# phrike.net
KiCad netlist of a schematic drawn in EAGLE
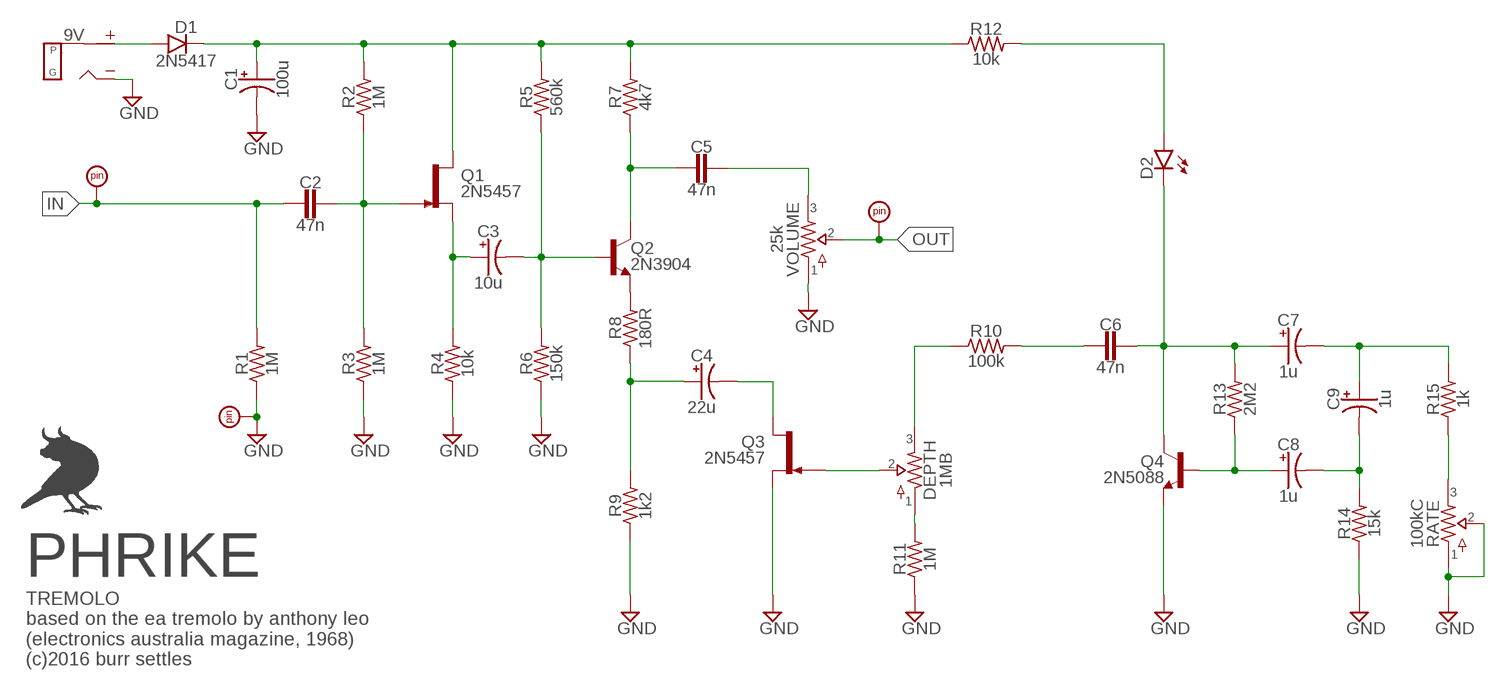
[diagram p0: schematic, sheet 1]

(export (version "E")
  (design (tool "Eeschema 10.0.6"))
  (components
    (comp (ref "9V")
      (value "DC_MONO")
      (footprint "eagle-import:DC")
      (libsource (lib "eagle-import") (part "DC_MONO"))
    )
    (comp (ref "C1")
      (value "100u")
      (footprint "eagle-import:063_025")
      (libsource (lib "eagle-import") (part "0631"))
    )
    (comp (ref "C2")
      (value "47n")
      (footprint "eagle-import:050X030_025_2")
      (libsource (lib "eagle-import") (part "CER/FILM2"))
    )
    (comp (ref "C3")
      (value "10u")
      (footprint "eagle-import:050_020_1")
      (libsource (lib "eagle-import") (part "0501"))
    )
    (comp (ref "C4")
      (value "22u")
      (footprint "eagle-import:050_020_1")
      (libsource (lib "eagle-import") (part "0501"))
    )
    (comp (ref "C5")
      (value "47n")
      (footprint "eagle-import:050X030_025_2")
      (libsource (lib "eagle-import") (part "CER/FILM2"))
    )
    (comp (ref "C6")
      (value "47n")
      (footprint "eagle-import:050X030_025_2")
      (libsource (lib "eagle-import") (part "CER/FILM2"))
    )
    (comp (ref "C7")
      (value "1u")
      (footprint "eagle-import:050_020_1")
      (libsource (lib "eagle-import") (part "0501"))
    )
    (comp (ref "C8")
      (value "1u")
      (footprint "eagle-import:050_020_1")
      (libsource (lib "eagle-import") (part "0501"))
    )
    (comp (ref "C9")
      (value "1u")
      (footprint "eagle-import:050_020_1")
      (libsource (lib "eagle-import") (part "0501"))
    )
    (comp (ref "D1")
      (value "2N5417")
      (footprint "eagle-import:DO41-3")
      (libsource (lib "eagle-import") (part "DO41.3"))
    )
    (comp (ref "D2")
      (value "LEDA")
      (footprint "eagle-import:3MM_A")
      (libsource (lib "eagle-import") (part "LEDA"))
    )
    (comp (ref "DEPTH")
      (value "1MB")
      (footprint "eagle-import:2262_TRIM")
      (libsource (lib "eagle-import") (part "POTSTRIM"))
    )
    (comp (ref "GND")
      (value "PADRND")
      (footprint "eagle-import:ROUND")
      (libsource (lib "eagle-import") (part "PADRND"))
    )
    (comp (ref "IN")
      (value "PADSQR")
      (footprint "eagle-import:SQUARE")
      (libsource (lib "eagle-import") (part "PADSQR"))
    )
    (comp (ref "OUT")
      (value "PADSQR")
      (footprint "eagle-import:SQUARE")
      (libsource (lib "eagle-import") (part "PADSQR"))
    )
    (comp (ref "Q1")
      (value "2N5457")
      (footprint "eagle-import:TO92-")
      (libsource (lib "eagle-import") (part "2N5457"))
    )
    (comp (ref "Q2")
      (value "2N3904")
      (footprint "eagle-import:TO92-L2")
      (libsource (lib "eagle-import") (part "2N3904L2"))
    )
    (comp (ref "Q3")
      (value "2N5457")
      (footprint "eagle-import:TO92-")
      (libsource (lib "eagle-import") (part "2N5457"))
    )
    (comp (ref "Q4")
      (value "2N5088")
      (footprint "eagle-import:TO92-")
      (libsource (lib "eagle-import") (part "2N5088"))
    )
    (comp (ref "R1")
      (value "1M")
      (footprint "eagle-import:R0207_3")
      (libsource (lib "eagle-import") (part "R_.3B"))
    )
    (comp (ref "R2")
      (value "1M")
      (footprint "eagle-import:R0207_3")
      (libsource (lib "eagle-import") (part "R_.3B"))
    )
    (comp (ref "R3")
      (value "1M")
      (footprint "eagle-import:R0207_3")
      (libsource (lib "eagle-import") (part "R_.3B"))
    )
    (comp (ref "R4")
      (value "10k")
      (footprint "eagle-import:R0207_3")
      (libsource (lib "eagle-import") (part "R_.3B"))
    )
    (comp (ref "R5")
      (value "560k")
      (footprint "eagle-import:R0207_3")
      (libsource (lib "eagle-import") (part "R_.3B"))
    )
    (comp (ref "R6")
      (value "150k")
      (footprint "eagle-import:R0207_3")
      (libsource (lib "eagle-import") (part "R_.3B"))
    )
    (comp (ref "R7")
      (value "4k7")
      (footprint "eagle-import:R0207_3")
      (libsource (lib "eagle-import") (part "R_.3B"))
    )
    (comp (ref "R8")
      (value "180R")
      (footprint "eagle-import:R0207_3")
      (libsource (lib "eagle-import") (part "R_.3B"))
    )
    (comp (ref "R9")
      (value "1k2")
      (footprint "eagle-import:R0207_3")
      (libsource (lib "eagle-import") (part "R_.3B"))
    )
    (comp (ref "R10")
      (value "100k")
      (footprint "eagle-import:R0207_3")
      (libsource (lib "eagle-import") (part "R_.3B"))
    )
    (comp (ref "R11")
      (value "1M")
      (footprint "eagle-import:R0207_3")
      (libsource (lib "eagle-import") (part "R_.3B"))
    )
    (comp (ref "R12")
      (value "10k")
      (footprint "eagle-import:R0207_3")
      (libsource (lib "eagle-import") (part "R_.3B"))
    )
    (comp (ref "R13")
      (value "2M2")
      (footprint "eagle-import:R0207_3")
      (libsource (lib "eagle-import") (part "R_.3B"))
    )
    (comp (ref "R14")
      (value "15k")
      (footprint "eagle-import:R0207_3")
      (libsource (lib "eagle-import") (part "R_.3B"))
    )
    (comp (ref "R15")
      (value "1k")
      (footprint "eagle-import:R0207_3")
      (libsource (lib "eagle-import") (part "R_.3B"))
    )
    (comp (ref "RATE")
      (value "100kC")
      (footprint "eagle-import:PADS_SMALL")
      (libsource (lib "eagle-import") (part "POTSSMALL_PADS"))
    )
    (comp (ref "VOLUME")
      (value "25k")
      (footprint "eagle-import:2262_TRIM")
      (libsource (lib "eagle-import") (part "POTSTRIM"))
    )
  )
  (nets
    (net (code "1") (name "GND") (class "Default")
      (node (ref "9V") (pin "S") (pinfunction "SLEEVE_S") (pintype "passive"))
      (node (ref "C1") (pin "-") (pinfunction "-_-") (pintype "passive"))
      (node (ref "GND") (pin "1") (pinfunction "P$1_1") (pintype "bidirectional"))
      (node (ref "Q3") (pin "2") (pinfunction "S_2") (pintype "passive"))
      (node (ref "Q4") (pin "3") (pinfunction "E_3") (pintype "passive"))
      (node (ref "R1") (pin "1") (pinfunction "1_1") (pintype "passive"))
      (node (ref "R11") (pin "1") (pinfunction "1_1") (pintype "passive"))
      (node (ref "R14") (pin "1") (pinfunction "1_1") (pintype "passive"))
      (node (ref "R3") (pin "1") (pinfunction "1_1") (pintype "passive"))
      (node (ref "R4") (pin "1") (pinfunction "1_1") (pintype "passive"))
      (node (ref "R6") (pin "1") (pinfunction "1_1") (pintype "passive"))
      (node (ref "R9") (pin "1") (pinfunction "1_1") (pintype "passive"))
      (node (ref "RATE") (pin "1") (pinfunction "1_1") (pintype "passive"))
      (node (ref "RATE") (pin "2") (pinfunction "2_2") (pintype "passive"))
      (node (ref "VOLUME") (pin "1") (pinfunction "1_1") (pintype "passive"))
    )
    (net (code "2") (name "IN") (class "Default")
      (node (ref "C2") (pin "2") (pinfunction "2_2") (pintype "passive"))
      (node (ref "IN") (pin "1") (pinfunction "P$1_1") (pintype "bidirectional"))
      (node (ref "R1") (pin "2") (pinfunction "2_2") (pintype "passive"))
    )
    (net (code "3") (name "Net-(9V-TIP)") (class "Default")
      (node (ref "9V") (pin "T") (pinfunction "TIP_T") (pintype "passive"))
      (node (ref "D1") (pin "A") (pinfunction "A_A") (pintype "passive"))
    )
    (net (code "4") (name "Net-(C4-Pad+)") (class "Default")
      (node (ref "C4") (pin "+") (pinfunction "+_+") (pintype "passive"))
      (node (ref "R8") (pin "1") (pinfunction "1_1") (pintype "passive"))
      (node (ref "R9") (pin "2") (pinfunction "2_2") (pintype "passive"))
    )
    (net (code "5") (name "Net-(C5-Pad1)") (class "Default")
      (node (ref "C5") (pin "1") (pinfunction "1_1") (pintype "passive"))
      (node (ref "VOLUME") (pin "3") (pinfunction "3_3") (pintype "passive"))
    )
    (net (code "6") (name "Net-(C6-Pad2)") (class "Default")
      (node (ref "C6") (pin "2") (pinfunction "2_2") (pintype "passive"))
      (node (ref "R10") (pin "2") (pinfunction "2_2") (pintype "passive"))
    )
    (net (code "7") (name "Net-(C7-Pad-)") (class "Default")
      (node (ref "C7") (pin "-") (pinfunction "-_-") (pintype "passive"))
      (node (ref "C9") (pin "+") (pinfunction "+_+") (pintype "passive"))
      (node (ref "R15") (pin "2") (pinfunction "2_2") (pintype "passive"))
    )
    (net (code "8") (name "Net-(C8-Pad-)") (class "Default")
      (node (ref "C8") (pin "-") (pinfunction "-_-") (pintype "passive"))
      (node (ref "C9") (pin "-") (pinfunction "-_-") (pintype "passive"))
      (node (ref "R14") (pin "2") (pinfunction "2_2") (pintype "passive"))
    )
    (net (code "9") (name "Net-(D2-C)") (class "Default")
      (node (ref "C6") (pin "1") (pinfunction "1_1") (pintype "passive"))
      (node (ref "C7") (pin "+") (pinfunction "+_+") (pintype "passive"))
      (node (ref "D2") (pin "K") (pinfunction "C_K") (pintype "passive"))
      (node (ref "Q4") (pin "1") (pinfunction "C_1") (pintype "passive"))
      (node (ref "R13") (pin "2") (pinfunction "2_2") (pintype "passive"))
    )
    (net (code "10") (name "Net-(D2-PadA)") (class "Default")
      (node (ref "D2") (pin "A") (pinfunction "A_A") (pintype "passive"))
      (node (ref "R12") (pin "2") (pinfunction "2_2") (pintype "passive"))
    )
    (net (code "11") (name "Net-(DEPTH-Pad1)") (class "Default")
      (node (ref "DEPTH") (pin "1") (pinfunction "1_1") (pintype "passive"))
      (node (ref "R11") (pin "2") (pinfunction "2_2") (pintype "passive"))
    )
    (net (code "12") (name "Net-(DEPTH-Pad3)") (class "Default")
      (node (ref "DEPTH") (pin "3") (pinfunction "3_3") (pintype "passive"))
      (node (ref "R10") (pin "1") (pinfunction "1_1") (pintype "passive"))
    )
    (net (code "13") (name "Net-(Q1-D)") (class "Default")
      (node (ref "C1") (pin "+") (pinfunction "+_+") (pintype "passive"))
      (node (ref "D1") (pin "C") (pinfunction "C_C") (pintype "passive"))
      (node (ref "Q1") (pin "3") (pinfunction "D_3") (pintype "passive"))
      (node (ref "R12") (pin "1") (pinfunction "1_1") (pintype "passive"))
      (node (ref "R2") (pin "2") (pinfunction "2_2") (pintype "passive"))
      (node (ref "R5") (pin "2") (pinfunction "2_2") (pintype "passive"))
      (node (ref "R7") (pin "2") (pinfunction "2_2") (pintype "passive"))
    )
    (net (code "14") (name "Net-(Q1-G)") (class "Default")
      (node (ref "C2") (pin "1") (pinfunction "1_1") (pintype "passive"))
      (node (ref "Q1") (pin "1") (pinfunction "G_1") (pintype "passive"))
      (node (ref "R2") (pin "1") (pinfunction "1_1") (pintype "passive"))
      (node (ref "R3") (pin "2") (pinfunction "2_2") (pintype "passive"))
    )
    (net (code "15") (name "Net-(Q1-S)") (class "Default")
      (node (ref "C3") (pin "+") (pinfunction "+_+") (pintype "passive"))
      (node (ref "Q1") (pin "2") (pinfunction "S_2") (pintype "passive"))
      (node (ref "R4") (pin "2") (pinfunction "2_2") (pintype "passive"))
    )
    (net (code "16") (name "Net-(Q2-B)") (class "Default")
      (node (ref "C3") (pin "-") (pinfunction "-_-") (pintype "passive"))
      (node (ref "Q2") (pin "2") (pinfunction "B_2") (pintype "passive"))
      (node (ref "R5") (pin "1") (pinfunction "1_1") (pintype "passive"))
      (node (ref "R6") (pin "2") (pinfunction "2_2") (pintype "passive"))
    )
    (net (code "17") (name "Net-(Q2-C)") (class "Default")
      (node (ref "C5") (pin "2") (pinfunction "2_2") (pintype "passive"))
      (node (ref "Q2") (pin "1") (pinfunction "C_1") (pintype "passive"))
      (node (ref "R7") (pin "1") (pinfunction "1_1") (pintype "passive"))
    )
    (net (code "18") (name "Net-(Q2-E)") (class "Default")
      (node (ref "Q2") (pin "3") (pinfunction "E_3") (pintype "passive"))
      (node (ref "R8") (pin "2") (pinfunction "2_2") (pintype "passive"))
    )
    (net (code "19") (name "Net-(Q3-D)") (class "Default")
      (node (ref "C4") (pin "-") (pinfunction "-_-") (pintype "passive"))
      (node (ref "Q3") (pin "3") (pinfunction "D_3") (pintype "passive"))
    )
    (net (code "20") (name "Net-(Q3-G)") (class "Default")
      (node (ref "DEPTH") (pin "2") (pinfunction "2_2") (pintype "passive"))
      (node (ref "Q3") (pin "1") (pinfunction "G_1") (pintype "passive"))
    )
    (net (code "21") (name "Net-(Q4-B)") (class "Default")
      (node (ref "C8") (pin "+") (pinfunction "+_+") (pintype "passive"))
      (node (ref "Q4") (pin "2") (pinfunction "B_2") (pintype "passive"))
      (node (ref "R13") (pin "1") (pinfunction "1_1") (pintype "passive"))
    )
    (net (code "22") (name "Net-(R15-Pad1)") (class "Default")
      (node (ref "R15") (pin "1") (pinfunction "1_1") (pintype "passive"))
      (node (ref "RATE") (pin "3") (pinfunction "3_3") (pintype "passive"))
    )
    (net (code "23") (name "OUT") (class "Default")
      (node (ref "OUT") (pin "1") (pinfunction "P$1_1") (pintype "bidirectional"))
      (node (ref "VOLUME") (pin "2") (pinfunction "2_2") (pintype "passive"))
    )
  )
)
